# EPS_Connectors_PC-104.net
KiCad netlist of a schematic drawn in Altium Designer
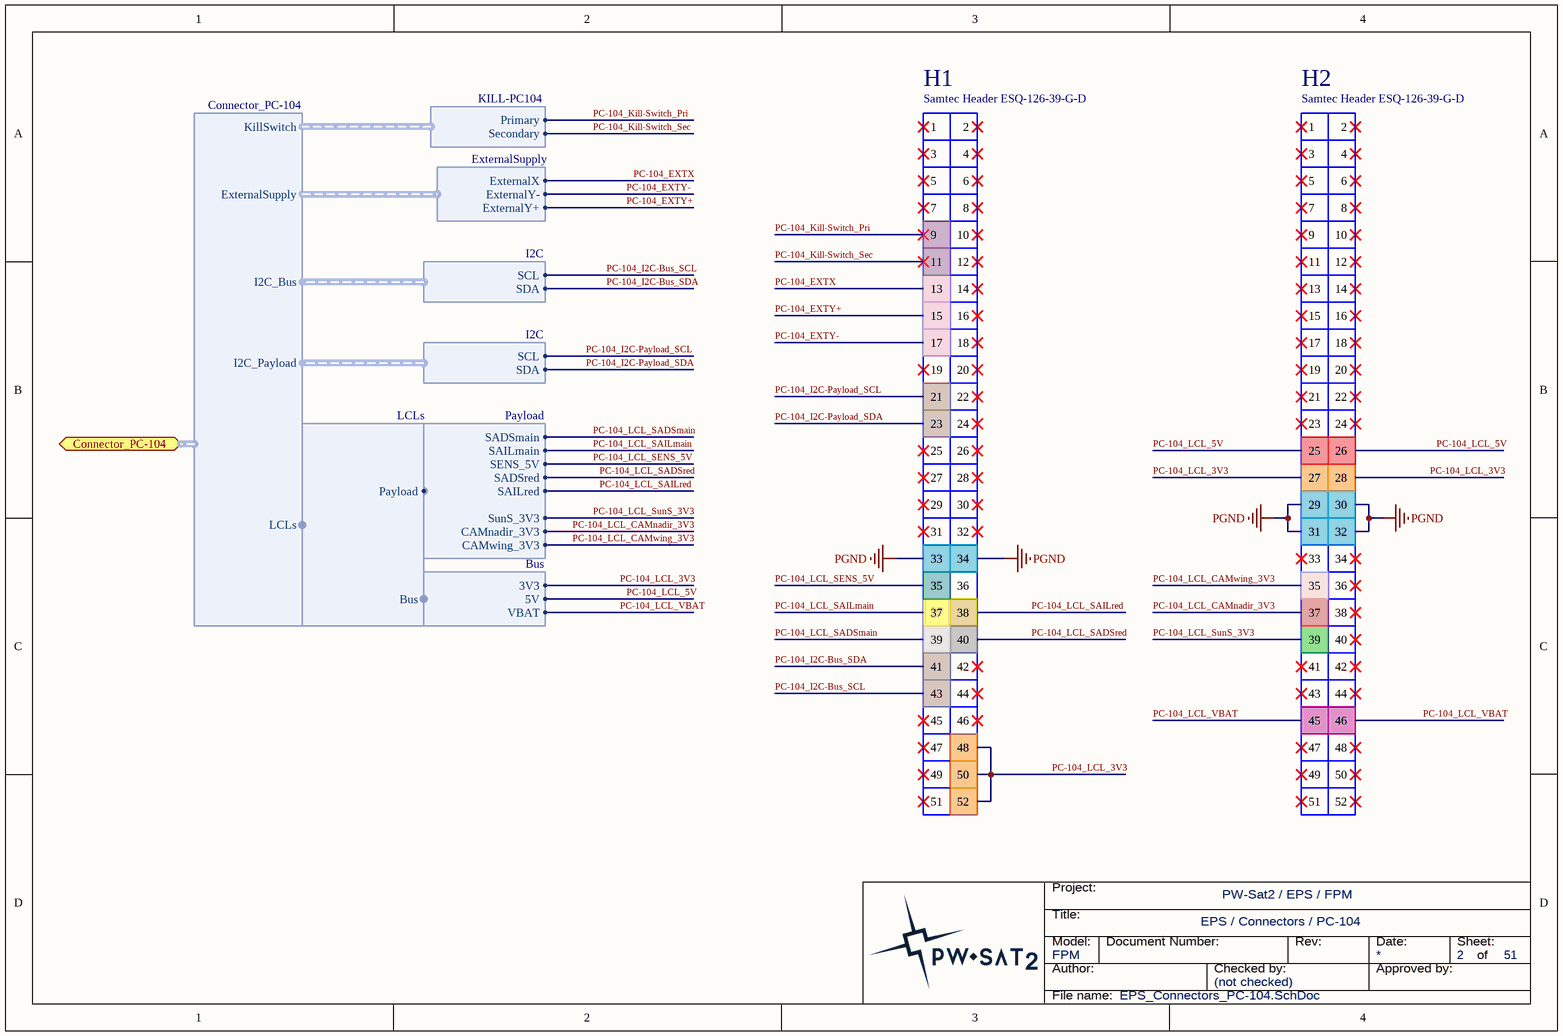
[diagram p0: EPS_Connectors_PC-104.SchDoc]

(export (version "E")
  (design (tool "Eeschema 10.0.6"))
  (components
    (comp (ref "H1")
      (value "Samtec Header ESQ-126-39-G-D")
      (footprint "Samtec_ESQ-126-39-G-D")
      (description "Samtec ESQ Series Header , 2.54mm pitch, 2x26pin. PC-104 Stack Connector.")
      (libsource (lib "connectors_printed-circuit-board") (part "Samtec_ESQ-126-xx-x-D"))
    )
    (comp (ref "H2")
      (value "Samtec Header ESQ-126-39-G-D")
      (footprint "Samtec_ESQ-126-39-G-D")
      (description "Samtec ESQ Series Header , 2.54mm pitch, 2x26pin. PC-104 Stack Connector.")
      (libsource (lib "connectors_printed-circuit-board") (part "Samtec_ESQ-126-xx-x-D"))
    )
  )
  (nets
    (net (code "6") (name "/PC-104_EXTX") (class "Default")
      (node (ref "H1") (pin "13") (pinfunction "13_13") (pintype "passive"))
    )
    (net (code "7") (name "/PC-104_EXTY+") (class "Default")
      (node (ref "H1") (pin "15") (pinfunction "15_15") (pintype "passive"))
    )
    (net (code "8") (name "/PC-104_EXTY-") (class "Default")
      (node (ref "H1") (pin "17") (pinfunction "17_17") (pintype "passive"))
    )
    (net (code "9") (name "/PC-104_I2C-Bus_SCL") (class "Default")
      (node (ref "H1") (pin "43") (pinfunction "43_43") (pintype "passive"))
    )
    (net (code "10") (name "/PC-104_I2C-Bus_SDA") (class "Default")
      (node (ref "H1") (pin "41") (pinfunction "41_41") (pintype "passive"))
    )
    (net (code "11") (name "/PC-104_I2C-Payload_SCL") (class "Default")
      (node (ref "H1") (pin "21") (pinfunction "21_21") (pintype "passive"))
    )
    (net (code "12") (name "/PC-104_I2C-Payload_SDA") (class "Default")
      (node (ref "H1") (pin "23") (pinfunction "23_23") (pintype "passive"))
    )
    (net (code "13") (name "/PC-104_Kill-Switch_Pri") (class "Default")
      (node (ref "H1") (pin "9") (pinfunction "9_9") (pintype "passive"))
    )
    (net (code "14") (name "/PC-104_Kill-Switch_Sec") (class "Default")
      (node (ref "H1") (pin "11") (pinfunction "11_11") (pintype "passive"))
    )
    (net (code "15") (name "/PC-104_LCL_3V3") (class "Default")
      (node (ref "H1") (pin "48") (pinfunction "48_48") (pintype "passive"))
      (node (ref "H1") (pin "50") (pinfunction "50_50") (pintype "passive"))
      (node (ref "H1") (pin "52") (pinfunction "52_52") (pintype "passive"))
      (node (ref "H2") (pin "27") (pinfunction "27_27") (pintype "passive"))
      (node (ref "H2") (pin "28") (pinfunction "28_28") (pintype "passive"))
    )
    (net (code "16") (name "/PC-104_LCL_5V") (class "Default")
      (node (ref "H2") (pin "25") (pinfunction "25_25") (pintype "passive"))
      (node (ref "H2") (pin "26") (pinfunction "26_26") (pintype "passive"))
    )
    (net (code "17") (name "/PC-104_LCL_CAMnadir_3V3") (class "Default")
      (node (ref "H2") (pin "37") (pinfunction "37_37") (pintype "passive"))
    )
    (net (code "18") (name "/PC-104_LCL_CAMwing_3V3") (class "Default")
      (node (ref "H2") (pin "35") (pinfunction "35_35") (pintype "passive"))
    )
    (net (code "19") (name "/PC-104_LCL_SADSmain") (class "Default")
      (node (ref "H1") (pin "39") (pinfunction "39_39") (pintype "passive"))
    )
    (net (code "20") (name "/PC-104_LCL_SADSred") (class "Default")
      (node (ref "H1") (pin "40") (pinfunction "40_40") (pintype "passive"))
    )
    (net (code "21") (name "/PC-104_LCL_SAILmain") (class "Default")
      (node (ref "H1") (pin "37") (pinfunction "37_37") (pintype "passive"))
    )
    (net (code "22") (name "/PC-104_LCL_SAILred") (class "Default")
      (node (ref "H1") (pin "38") (pinfunction "38_38") (pintype "passive"))
    )
    (net (code "23") (name "/PC-104_LCL_SENS_5V") (class "Default")
      (node (ref "H1") (pin "35") (pinfunction "35_35") (pintype "passive"))
    )
    (net (code "24") (name "/PC-104_LCL_SunS_3V3") (class "Default")
      (node (ref "H2") (pin "39") (pinfunction "39_39") (pintype "passive"))
    )
    (net (code "25") (name "/PC-104_LCL_VBAT") (class "Default")
      (node (ref "H2") (pin "45") (pinfunction "45_45") (pintype "passive"))
      (node (ref "H2") (pin "46") (pinfunction "46_46") (pintype "passive"))
    )
    (net (code "29") (name "PGND") (class "Default")
      (node (ref "H1") (pin "33") (pinfunction "33_33") (pintype "passive"))
      (node (ref "H1") (pin "34") (pinfunction "34_34") (pintype "passive"))
      (node (ref "H2") (pin "29") (pinfunction "29_29") (pintype "passive"))
      (node (ref "H2") (pin "30") (pinfunction "30_30") (pintype "passive"))
      (node (ref "H2") (pin "31") (pinfunction "31_31") (pintype "passive"))
      (node (ref "H2") (pin "32") (pinfunction "32_32") (pintype "passive"))
    )
    (net (code "30") (name "unconnected-(H1-Pad1)") (class "Default")
      (node (ref "H1") (pin "1") (pinfunction "1_1") (pintype "passive+no_connect"))
    )
    (net (code "31") (name "unconnected-(H1-Pad2)") (class "Default")
      (node (ref "H1") (pin "2") (pinfunction "2_2") (pintype "passive+no_connect"))
    )
    (net (code "32") (name "unconnected-(H1-Pad3)") (class "Default")
      (node (ref "H1") (pin "3") (pinfunction "3_3") (pintype "passive+no_connect"))
    )
    (net (code "33") (name "unconnected-(H1-Pad4)") (class "Default")
      (node (ref "H1") (pin "4") (pinfunction "4_4") (pintype "passive+no_connect"))
    )
    (net (code "34") (name "unconnected-(H1-Pad5)") (class "Default")
      (node (ref "H1") (pin "5") (pinfunction "5_5") (pintype "passive+no_connect"))
    )
    (net (code "35") (name "unconnected-(H1-Pad6)") (class "Default")
      (node (ref "H1") (pin "6") (pinfunction "6_6") (pintype "passive+no_connect"))
    )
    (net (code "36") (name "unconnected-(H1-Pad7)") (class "Default")
      (node (ref "H1") (pin "7") (pinfunction "7_7") (pintype "passive+no_connect"))
    )
    (net (code "37") (name "unconnected-(H1-Pad8)") (class "Default")
      (node (ref "H1") (pin "8") (pinfunction "8_8") (pintype "passive+no_connect"))
    )
    (net (code "38") (name "unconnected-(H1-Pad10)") (class "Default")
      (node (ref "H1") (pin "10") (pinfunction "10_10") (pintype "passive+no_connect"))
    )
    (net (code "39") (name "unconnected-(H1-Pad12)") (class "Default")
      (node (ref "H1") (pin "12") (pinfunction "12_12") (pintype "passive+no_connect"))
    )
    (net (code "40") (name "unconnected-(H1-Pad14)") (class "Default")
      (node (ref "H1") (pin "14") (pinfunction "14_14") (pintype "passive+no_connect"))
    )
    (net (code "41") (name "unconnected-(H1-Pad16)") (class "Default")
      (node (ref "H1") (pin "16") (pinfunction "16_16") (pintype "passive+no_connect"))
    )
    (net (code "42") (name "unconnected-(H1-Pad18)") (class "Default")
      (node (ref "H1") (pin "18") (pinfunction "18_18") (pintype "passive+no_connect"))
    )
    (net (code "43") (name "unconnected-(H1-Pad19)") (class "Default")
      (node (ref "H1") (pin "19") (pinfunction "19_19") (pintype "passive+no_connect"))
    )
    (net (code "44") (name "unconnected-(H1-Pad20)") (class "Default")
      (node (ref "H1") (pin "20") (pinfunction "20_20") (pintype "passive+no_connect"))
    )
    (net (code "45") (name "unconnected-(H1-Pad22)") (class "Default")
      (node (ref "H1") (pin "22") (pinfunction "22_22") (pintype "passive+no_connect"))
    )
    (net (code "46") (name "unconnected-(H1-Pad24)") (class "Default")
      (node (ref "H1") (pin "24") (pinfunction "24_24") (pintype "passive+no_connect"))
    )
    (net (code "47") (name "unconnected-(H1-Pad25)") (class "Default")
      (node (ref "H1") (pin "25") (pinfunction "25_25") (pintype "passive+no_connect"))
    )
    (net (code "48") (name "unconnected-(H1-Pad26)") (class "Default")
      (node (ref "H1") (pin "26") (pinfunction "26_26") (pintype "passive+no_connect"))
    )
    (net (code "49") (name "unconnected-(H1-Pad27)") (class "Default")
      (node (ref "H1") (pin "27") (pinfunction "27_27") (pintype "passive+no_connect"))
    )
    (net (code "50") (name "unconnected-(H1-Pad28)") (class "Default")
      (node (ref "H1") (pin "28") (pinfunction "28_28") (pintype "passive+no_connect"))
    )
    (net (code "51") (name "unconnected-(H1-Pad29)") (class "Default")
      (node (ref "H1") (pin "29") (pinfunction "29_29") (pintype "passive+no_connect"))
    )
    (net (code "52") (name "unconnected-(H1-Pad30)") (class "Default")
      (node (ref "H1") (pin "30") (pinfunction "30_30") (pintype "passive+no_connect"))
    )
    (net (code "53") (name "unconnected-(H1-Pad31)") (class "Default")
      (node (ref "H1") (pin "31") (pinfunction "31_31") (pintype "passive+no_connect"))
    )
    (net (code "54") (name "unconnected-(H1-Pad32)") (class "Default")
      (node (ref "H1") (pin "32") (pinfunction "32_32") (pintype "passive+no_connect"))
    )
    (net (code "55") (name "unconnected-(H1-Pad36)") (class "Default")
      (node (ref "H1") (pin "36") (pinfunction "36_36") (pintype "passive"))
    )
    (net (code "56") (name "unconnected-(H1-Pad42)") (class "Default")
      (node (ref "H1") (pin "42") (pinfunction "42_42") (pintype "passive+no_connect"))
    )
    (net (code "57") (name "unconnected-(H1-Pad44)") (class "Default")
      (node (ref "H1") (pin "44") (pinfunction "44_44") (pintype "passive+no_connect"))
    )
    (net (code "58") (name "unconnected-(H1-Pad45)") (class "Default")
      (node (ref "H1") (pin "45") (pinfunction "45_45") (pintype "passive+no_connect"))
    )
    (net (code "59") (name "unconnected-(H1-Pad46)") (class "Default")
      (node (ref "H1") (pin "46") (pinfunction "46_46") (pintype "passive+no_connect"))
    )
    (net (code "60") (name "unconnected-(H1-Pad47)") (class "Default")
      (node (ref "H1") (pin "47") (pinfunction "47_47") (pintype "passive+no_connect"))
    )
    (net (code "61") (name "unconnected-(H1-Pad49)") (class "Default")
      (node (ref "H1") (pin "49") (pinfunction "49_49") (pintype "passive+no_connect"))
    )
    (net (code "62") (name "unconnected-(H1-Pad51)") (class "Default")
      (node (ref "H1") (pin "51") (pinfunction "51_51") (pintype "passive+no_connect"))
    )
    (net (code "63") (name "unconnected-(H2-Pad1)") (class "Default")
      (node (ref "H2") (pin "1") (pinfunction "1_1") (pintype "passive+no_connect"))
    )
    (net (code "64") (name "unconnected-(H2-Pad2)") (class "Default")
      (node (ref "H2") (pin "2") (pinfunction "2_2") (pintype "passive+no_connect"))
    )
    (net (code "65") (name "unconnected-(H2-Pad3)") (class "Default")
      (node (ref "H2") (pin "3") (pinfunction "3_3") (pintype "passive+no_connect"))
    )
    (net (code "66") (name "unconnected-(H2-Pad4)") (class "Default")
      (node (ref "H2") (pin "4") (pinfunction "4_4") (pintype "passive+no_connect"))
    )
    (net (code "67") (name "unconnected-(H2-Pad5)") (class "Default")
      (node (ref "H2") (pin "5") (pinfunction "5_5") (pintype "passive+no_connect"))
    )
    (net (code "68") (name "unconnected-(H2-Pad6)") (class "Default")
      (node (ref "H2") (pin "6") (pinfunction "6_6") (pintype "passive+no_connect"))
    )
    (net (code "69") (name "unconnected-(H2-Pad7)") (class "Default")
      (node (ref "H2") (pin "7") (pinfunction "7_7") (pintype "passive+no_connect"))
    )
    (net (code "70") (name "unconnected-(H2-Pad8)") (class "Default")
      (node (ref "H2") (pin "8") (pinfunction "8_8") (pintype "passive+no_connect"))
    )
    (net (code "71") (name "unconnected-(H2-Pad9)") (class "Default")
      (node (ref "H2") (pin "9") (pinfunction "9_9") (pintype "passive+no_connect"))
    )
    (net (code "72") (name "unconnected-(H2-Pad10)") (class "Default")
      (node (ref "H2") (pin "10") (pinfunction "10_10") (pintype "passive+no_connect"))
    )
    (net (code "73") (name "unconnected-(H2-Pad11)") (class "Default")
      (node (ref "H2") (pin "11") (pinfunction "11_11") (pintype "passive+no_connect"))
    )
    (net (code "74") (name "unconnected-(H2-Pad12)") (class "Default")
      (node (ref "H2") (pin "12") (pinfunction "12_12") (pintype "passive+no_connect"))
    )
    (net (code "75") (name "unconnected-(H2-Pad13)") (class "Default")
      (node (ref "H2") (pin "13") (pinfunction "13_13") (pintype "passive+no_connect"))
    )
    (net (code "76") (name "unconnected-(H2-Pad14)") (class "Default")
      (node (ref "H2") (pin "14") (pinfunction "14_14") (pintype "passive+no_connect"))
    )
    (net (code "77") (name "unconnected-(H2-Pad15)") (class "Default")
      (node (ref "H2") (pin "15") (pinfunction "15_15") (pintype "passive+no_connect"))
    )
    (net (code "78") (name "unconnected-(H2-Pad16)") (class "Default")
      (node (ref "H2") (pin "16") (pinfunction "16_16") (pintype "passive+no_connect"))
    )
    (net (code "79") (name "unconnected-(H2-Pad17)") (class "Default")
      (node (ref "H2") (pin "17") (pinfunction "17_17") (pintype "passive+no_connect"))
    )
    (net (code "80") (name "unconnected-(H2-Pad18)") (class "Default")
      (node (ref "H2") (pin "18") (pinfunction "18_18") (pintype "passive+no_connect"))
    )
    (net (code "81") (name "unconnected-(H2-Pad19)") (class "Default")
      (node (ref "H2") (pin "19") (pinfunction "19_19") (pintype "passive+no_connect"))
    )
    (net (code "82") (name "unconnected-(H2-Pad20)") (class "Default")
      (node (ref "H2") (pin "20") (pinfunction "20_20") (pintype "passive+no_connect"))
    )
    (net (code "83") (name "unconnected-(H2-Pad21)") (class "Default")
      (node (ref "H2") (pin "21") (pinfunction "21_21") (pintype "passive+no_connect"))
    )
    (net (code "84") (name "unconnected-(H2-Pad22)") (class "Default")
      (node (ref "H2") (pin "22") (pinfunction "22_22") (pintype "passive+no_connect"))
    )
    (net (code "85") (name "unconnected-(H2-Pad23)") (class "Default")
      (node (ref "H2") (pin "23") (pinfunction "23_23") (pintype "passive+no_connect"))
    )
    (net (code "86") (name "unconnected-(H2-Pad24)") (class "Default")
      (node (ref "H2") (pin "24") (pinfunction "24_24") (pintype "passive+no_connect"))
    )
    (net (code "87") (name "unconnected-(H2-Pad33)") (class "Default")
      (node (ref "H2") (pin "33") (pinfunction "33_33") (pintype "passive+no_connect"))
    )
    (net (code "88") (name "unconnected-(H2-Pad34)") (class "Default")
      (node (ref "H2") (pin "34") (pinfunction "34_34") (pintype "passive+no_connect"))
    )
    (net (code "89") (name "unconnected-(H2-Pad36)") (class "Default")
      (node (ref "H2") (pin "36") (pinfunction "36_36") (pintype "passive+no_connect"))
    )
    (net (code "90") (name "unconnected-(H2-Pad38)") (class "Default")
      (node (ref "H2") (pin "38") (pinfunction "38_38") (pintype "passive+no_connect"))
    )
    (net (code "91") (name "unconnected-(H2-Pad40)") (class "Default")
      (node (ref "H2") (pin "40") (pinfunction "40_40") (pintype "passive+no_connect"))
    )
    (net (code "92") (name "unconnected-(H2-Pad41)") (class "Default")
      (node (ref "H2") (pin "41") (pinfunction "41_41") (pintype "passive+no_connect"))
    )
    (net (code "93") (name "unconnected-(H2-Pad42)") (class "Default")
      (node (ref "H2") (pin "42") (pinfunction "42_42") (pintype "passive+no_connect"))
    )
    (net (code "94") (name "unconnected-(H2-Pad43)") (class "Default")
      (node (ref "H2") (pin "43") (pinfunction "43_43") (pintype "passive+no_connect"))
    )
    (net (code "95") (name "unconnected-(H2-Pad44)") (class "Default")
      (node (ref "H2") (pin "44") (pinfunction "44_44") (pintype "passive+no_connect"))
    )
    (net (code "96") (name "unconnected-(H2-Pad47)") (class "Default")
      (node (ref "H2") (pin "47") (pinfunction "47_47") (pintype "passive+no_connect"))
    )
    (net (code "97") (name "unconnected-(H2-Pad48)") (class "Default")
      (node (ref "H2") (pin "48") (pinfunction "48_48") (pintype "passive+no_connect"))
    )
    (net (code "98") (name "unconnected-(H2-Pad49)") (class "Default")
      (node (ref "H2") (pin "49") (pinfunction "49_49") (pintype "passive+no_connect"))
    )
    (net (code "99") (name "unconnected-(H2-Pad50)") (class "Default")
      (node (ref "H2") (pin "50") (pinfunction "50_50") (pintype "passive+no_connect"))
    )
    (net (code "100") (name "unconnected-(H2-Pad51)") (class "Default")
      (node (ref "H2") (pin "51") (pinfunction "51_51") (pintype "passive+no_connect"))
    )
    (net (code "101") (name "unconnected-(H2-Pad52)") (class "Default")
      (node (ref "H2") (pin "52") (pinfunction "52_52") (pintype "passive+no_connect"))
    )
  )
)
